# SW6106_A_B_C_Lighting_LED.net
KiCad netlist of a schematic drawn in Altium Designer
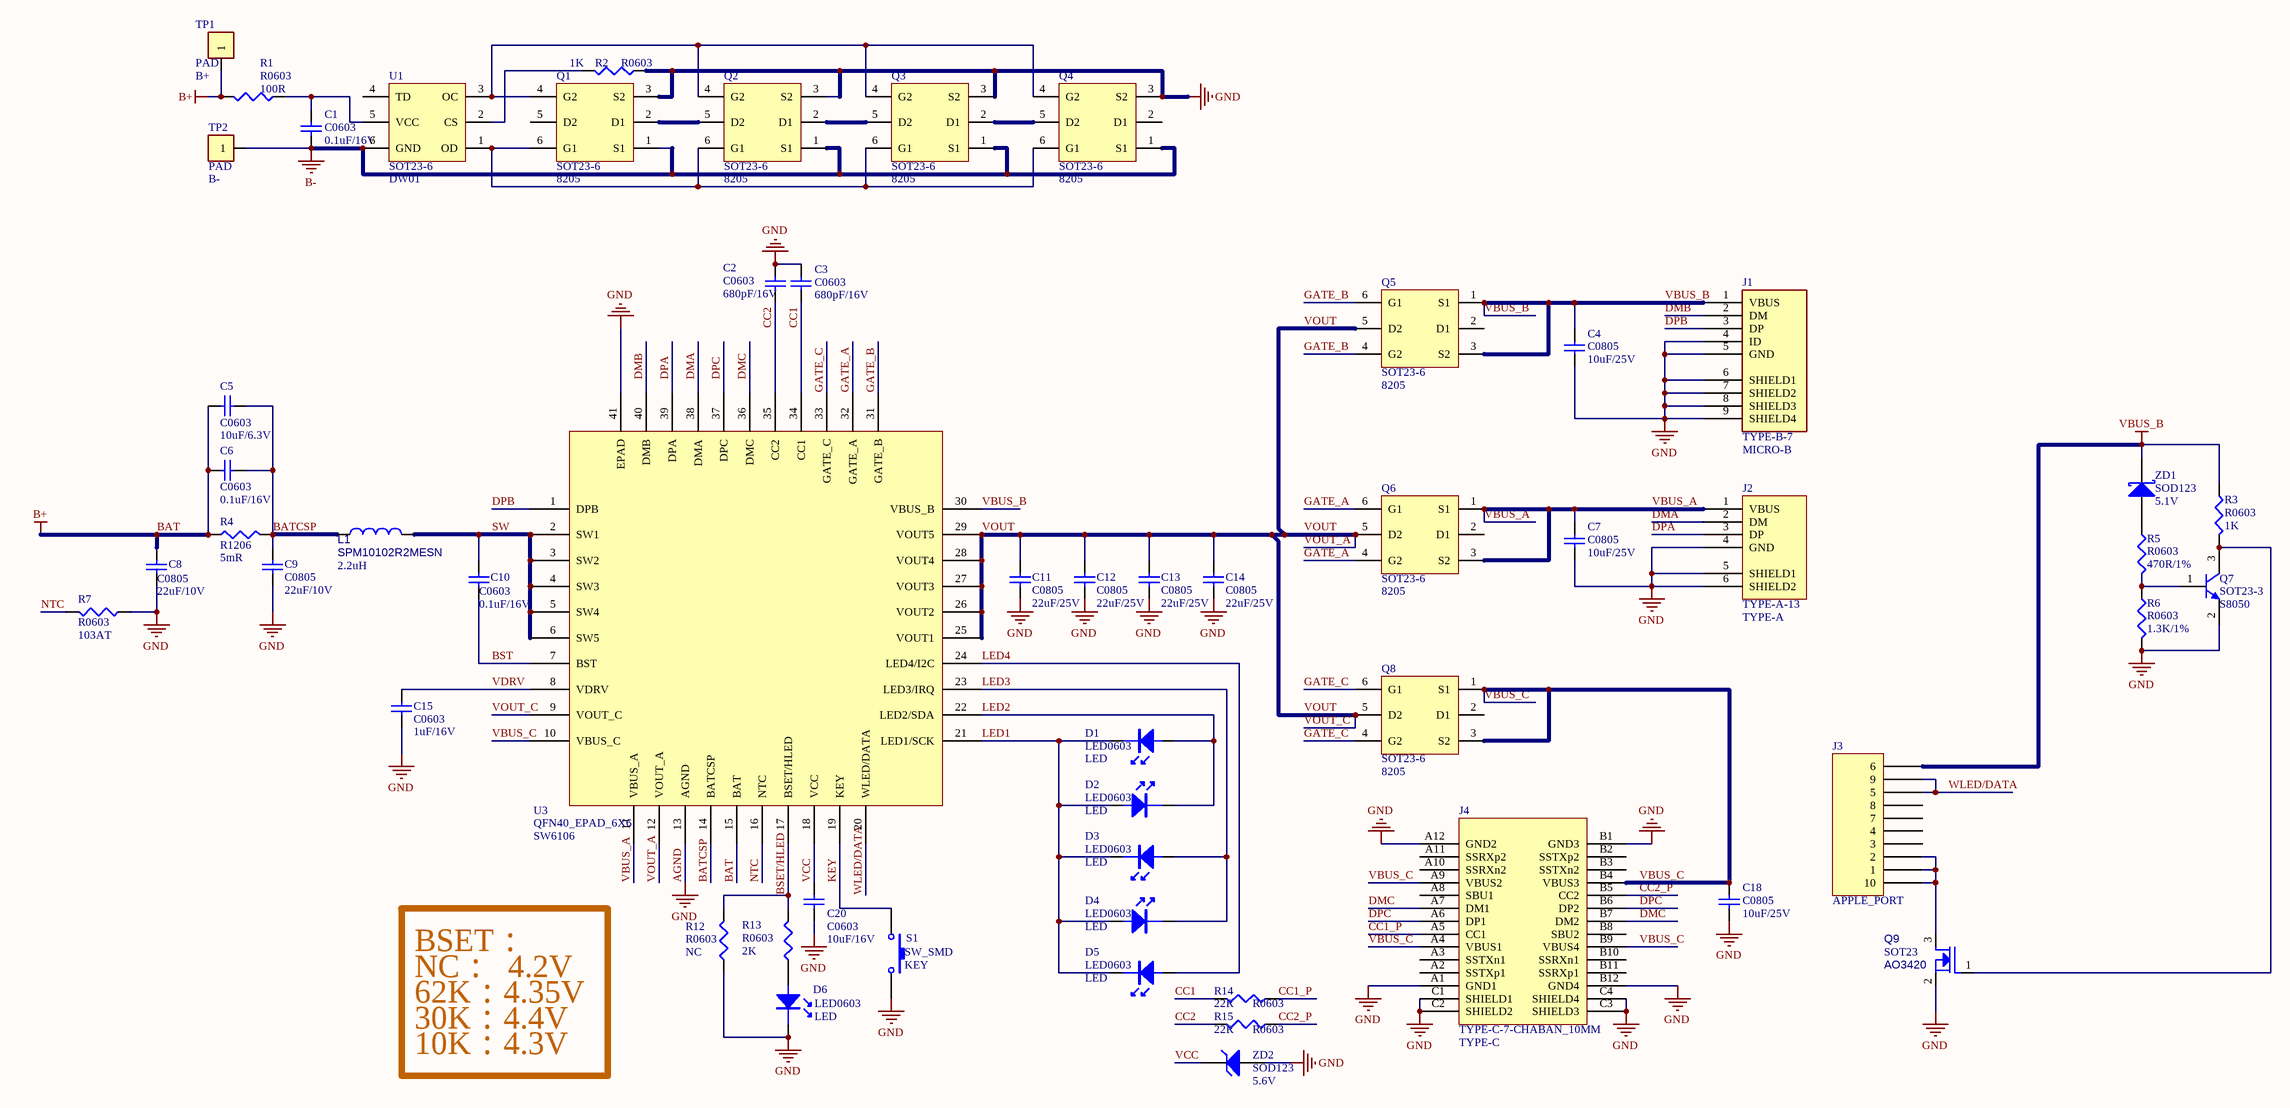
[diagram p0: SW6106+A+B+C+内部解密Lighting+LED.SchDoc]

(export (version "E")
  (design (tool "Eeschema 10.0.6"))
  (components
    (comp (ref "C1")
      (value "C0603")
      (footprint "C0603")
      (description "Capacitor")
      (fields (field (name "ALTIUM_VALUE") "0.1uF/16V") (field (name "PUBLISHER") "Altium Limited"))
      (libsource (lib "*") (part "Cap"))
    )
    (comp (ref "C2")
      (value "C0603")
      (footprint "C0603")
      (description "Capacitor")
      (fields (field (name "ALTIUM_VALUE") "680pF/16V") (field (name "PUBLISHER") "Altium Limited"))
      (libsource (lib "*") (part "CAP0603"))
    )
    (comp (ref "C3")
      (value "C0603")
      (footprint "C0603")
      (description "Capacitor")
      (fields (field (name "ALTIUM_VALUE") "680pF/16V") (field (name "PUBLISHER") "Altium Limited"))
      (libsource (lib "*") (part "CAP0603"))
    )
    (comp (ref "C4")
      (value "C0805")
      (footprint "C0805")
      (description "Capacitor")
      (fields (field (name "ALTIUM_VALUE") "10uF/25V") (field (name "PUBLISHER") "Altium Limited"))
      (libsource (lib "*") (part "CAP0603"))
    )
    (comp (ref "C5")
      (value "C0603")
      (footprint "C0603")
      (description "Capacitor")
      (fields (field (name "ALTIUM_VALUE") "10uF/6.3V") (field (name "PUBLISHER") "Altium Limited"))
      (libsource (lib "*") (part "CAP0603"))
    )
    (comp (ref "C6")
      (value "C0603")
      (footprint "C0603")
      (description "Capacitor")
      (fields (field (name "ALTIUM_VALUE") "0.1uF/16V") (field (name "PUBLISHER") "Altium Limited"))
      (libsource (lib "*") (part "CAP0603"))
    )
    (comp (ref "C7")
      (value "C0805")
      (footprint "C0805")
      (description "Capacitor")
      (fields (field (name "ALTIUM_VALUE") "10uF/25V") (field (name "PUBLISHER") "Altium Limited"))
      (libsource (lib "*") (part "CAP0603"))
    )
    (comp (ref "C8")
      (value "C0805")
      (footprint "C0805")
      (description "Capacitor")
      (fields (field (name "ALTIUM_VALUE") "22uF/10V") (field (name "PUBLISHER") "Altium Limited"))
      (libsource (lib "*") (part "CAP0805"))
    )
    (comp (ref "C9")
      (value "C0805")
      (footprint "C0805")
      (description "Capacitor")
      (fields (field (name "ALTIUM_VALUE") "22uF/10V") (field (name "PUBLISHER") "Altium Limited"))
      (libsource (lib "*") (part "CAP0805"))
    )
    (comp (ref "C10")
      (value "C0603")
      (footprint "C0603")
      (description "Capacitor")
      (fields (field (name "ALTIUM_VALUE") "0.1uF/16V") (field (name "PUBLISHER") "Altium Limited"))
      (libsource (lib "*") (part "CAP0603"))
    )
    (comp (ref "C11")
      (value "C0805")
      (footprint "C0805")
      (description "Capacitor")
      (fields (field (name "ALTIUM_VALUE") "22uF/25V") (field (name "PUBLISHER") "Altium Limited"))
      (libsource (lib "*") (part "CAP0805"))
    )
    (comp (ref "C12")
      (value "C0805")
      (footprint "C0805")
      (description "Capacitor")
      (fields (field (name "ALTIUM_VALUE") "22uF/25V") (field (name "PUBLISHER") "Altium Limited"))
      (libsource (lib "*") (part "CAP0805"))
    )
    (comp (ref "C13")
      (value "C0805")
      (footprint "C0805")
      (description "Capacitor")
      (fields (field (name "ALTIUM_VALUE") "22uF/25V") (field (name "PUBLISHER") "Altium Limited"))
      (libsource (lib "*") (part "CAP0805"))
    )
    (comp (ref "C14")
      (value "C0805")
      (footprint "C0805")
      (description "Capacitor")
      (fields (field (name "ALTIUM_VALUE") "22uF/25V") (field (name "PUBLISHER") "Altium Limited"))
      (libsource (lib "*") (part "CAP0805"))
    )
    (comp (ref "C15")
      (value "C0603")
      (footprint "C0603")
      (description "Capacitor")
      (fields (field (name "ALTIUM_VALUE") "1uF/16V") (field (name "PUBLISHER") "Altium Limited"))
      (libsource (lib "*") (part "CAP0603"))
    )
    (comp (ref "C18")
      (value "C0805")
      (footprint "C0805")
      (description "Capacitor")
      (fields (field (name "ALTIUM_VALUE") "10uF/25V") (field (name "PUBLISHER") "Altium Limited"))
      (libsource (lib "*") (part "CAP0603"))
    )
    (comp (ref "C20")
      (value "C0603")
      (footprint "C0603")
      (description "Capacitor")
      (fields (field (name "ALTIUM_VALUE") "10uF/16V") (field (name "PUBLISHER") "Altium Limited"))
      (libsource (lib "*") (part "CAP0603"))
    )
    (comp (ref "D1") (value "LED") (footprint "LED0603") (libsource (lib "*") (part "LED")))
    (comp (ref "D2") (value "LED") (footprint "LED0603") (libsource (lib "*") (part "LED")))
    (comp (ref "D3") (value "LED") (footprint "LED0603") (libsource (lib "*") (part "LED")))
    (comp (ref "D4") (value "LED") (footprint "LED0603") (libsource (lib "*") (part "LED")))
    (comp (ref "D5") (value "LED") (footprint "LED0603") (libsource (lib "*") (part "LED")))
    (comp (ref "D6") (value "LED") (footprint "LED0603") (libsource (lib "*") (part "LED")))
    (comp (ref "J1")
      (value "MICRO-B")
      (footprint "TYPE-B-7")
      (fields (field (name "FOOTPRINTF") "TYPE-B-7") (field (name "Comment") "USB_MICRO_B"))
      (libsource (lib "*") (part "USB_MICRO_B"))
    )
    (comp (ref "J2")
      (value "TYPE-A")
      (footprint "TYPE-A-13")
      (fields (field (name "FOOTPRINF") "TYPE-A-13") (field (name "Comment") "TYPE-A-1"))
      (libsource (lib "*") (part "TYPE-A-1"))
    )
    (comp (ref "J3") (value "APPLE_PORT") (libsource (lib "TEST") (part "APPLE_PORT")))
    (comp (ref "J4")
      (value "TYPE-C")
      (footprint "TYPE-C-7-CHABAN_10MM")
      (libsource (lib "*") (part "TYPE-C"))
    )
    (comp (ref "L1")
      (value "SPM10102R2MESN")
      (footprint "INDUCTOR_SPM1010")
      (fields (field (name "ALTIUM_VALUE") "2.2uH"))
      (libsource (lib "*") (part "INDUCTOR"))
    )
    (comp (ref "Q1")
      (value "8205")
      (footprint "SOT23-6")
      (fields (field (name "FOOTPRINF") "SOT23-6"))
      (libsource (lib "") (part "8205B_1"))
    )
    (comp (ref "Q2")
      (value "8205")
      (footprint "SOT23-6")
      (fields (field (name "FOOTPRINF") "SOT23-6"))
      (libsource (lib "") (part "8205B_1"))
    )
    (comp (ref "Q3")
      (value "8205")
      (footprint "SOT23-6")
      (fields (field (name "FOOTPRINF") "SOT23-6"))
      (libsource (lib "") (part "8205B_1"))
    )
    (comp (ref "Q4")
      (value "8205")
      (footprint "SOT23-6")
      (fields (field (name "FOOTPRINF") "SOT23-6"))
      (libsource (lib "") (part "8205B_1"))
    )
    (comp (ref "Q5")
      (value "8205")
      (footprint "SOT23-6")
      (fields (field (name "FOOTPRINF") "SOT23-6"))
      (libsource (lib "*") (part "8205B"))
    )
    (comp (ref "Q6")
      (value "8205")
      (footprint "SOT23-6")
      (fields (field (name "FOOTPRINF") "SOT23-6"))
      (libsource (lib "*") (part "8205B"))
    )
    (comp (ref "Q7")
      (value "S8050")
      (footprint "SOT23-3")
      (description "NPN General Purpose Amplifier")
      (fields (field (name "PUBLISHER") "Altium Limited"))
      (libsource (lib "Miscellaneous Devices") (part "2N3904"))
    )
    (comp (ref "Q8")
      (value "8205")
      (footprint "SOT23-6")
      (fields (field (name "FOOTPRINF") "SOT23-6"))
      (libsource (lib "*") (part "8205B"))
    )
    (comp (ref "Q9") (value "AO3420") (footprint "SOT23") (libsource (lib "智融科技有限公司原理图库") (part "MOSFET_N")))
    (comp (ref "R1")
      (value "R0603")
      (footprint "R0603")
      (description "Resistor")
      (fields (field (name "ALTIUM_VALUE") "100R") (field (name "PUBLISHER") "Altium Limited"))
      (libsource (lib "*") (part "Res3"))
    )
    (comp (ref "R2")
      (value "R0603")
      (footprint "R0603")
      (description "Resistor")
      (fields (field (name "ALTIUM_VALUE") "1K") (field (name "PUBLISHER") "Altium Limited"))
      (libsource (lib "*") (part "Res3"))
    )
    (comp (ref "R3")
      (value "R0603")
      (footprint "R0603")
      (description "Resistor")
      (fields (field (name "ALTIUM_VALUE") "1K") (field (name "PUBLISHER") "Altium Limited"))
      (libsource (lib "Miscellaneous Devices") (part "Res3"))
    )
    (comp (ref "R4")
      (value "R1206")
      (footprint "R1206")
      (description "Resistor")
      (fields (field (name "ALTIUM_VALUE") "5mR") (field (name "PUBLISHER") "Altium Limited"))
      (libsource (lib "*") (part "RES"))
    )
    (comp (ref "R5")
      (value "R0603")
      (footprint "R0603")
      (description "Resistor")
      (fields (field (name "ALTIUM_VALUE") "470R/1%") (field (name "PUBLISHER") "Altium Limited"))
      (libsource (lib "Miscellaneous Devices") (part "Res3"))
    )
    (comp (ref "R6")
      (value "R0603")
      (footprint "R0603")
      (description "Resistor")
      (fields (field (name "ALTIUM_VALUE") "1.3K/1%") (field (name "PUBLISHER") "Altium Limited"))
      (libsource (lib "Miscellaneous Devices") (part "Res3"))
    )
    (comp (ref "R7")
      (value "R0603")
      (footprint "R0603")
      (description "Resistor")
      (fields (field (name "ALTIUM_VALUE") "103AT") (field (name "PUBLISHER") "Altium Limited"))
      (libsource (lib "*") (part "RES"))
    )
    (comp (ref "R12")
      (value "R0603")
      (footprint "R0603")
      (description "Resistor")
      (fields (field (name "ALTIUM_VALUE") "NC") (field (name "PUBLISHER") "Altium Limited"))
      (libsource (lib "*") (part "RES"))
    )
    (comp (ref "R13")
      (value "R0603")
      (footprint "R0603")
      (description "Resistor")
      (fields (field (name "ALTIUM_VALUE") "2K") (field (name "PUBLISHER") "Altium Limited"))
      (libsource (lib "*") (part "RES"))
    )
    (comp (ref "R14")
      (value "R0603")
      (footprint "R0603")
      (description "Resistor")
      (fields (field (name "ALTIUM_VALUE") "22R") (field (name "PUBLISHER") "Altium Limited"))
      (libsource (lib "*") (part "RES"))
    )
    (comp (ref "R15")
      (value "R0603")
      (footprint "R0603")
      (description "Resistor")
      (fields (field (name "ALTIUM_VALUE") "22R") (field (name "PUBLISHER") "Altium Limited"))
      (libsource (lib "*") (part "RES"))
    )
    (comp (ref "S1")
      (value "KEY")
      (footprint "SW_SMD")
      (fields (field (name "FOOTPRINF") "SW_SMD"))
      (libsource (lib "*") (part "SW K"))
    )
    (comp (ref "TP1") (value "B+") (footprint "PAD") (libsource (lib "*") (part "Test Point")))
    (comp (ref "TP2") (value "B-") (footprint "PAD") (libsource (lib "") (part "Test Point_1")))
    (comp (ref "U1")
      (value "DW01")
      (footprint "SOT23-6")
      (fields (field (name "FOOTPRINF") "SOT23-6"))
      (libsource (lib "*") (part "DW01"))
    )
    (comp (ref "U3")
      (value "SW6106")
      (footprint "QFN40_EPAD_6X6")
      (libsource (lib "TEST") (part "SW6106_AFC"))
    )
    (comp (ref "ZD1")
      (value "5.1V")
      (footprint "SOD123")
      (description "Schottky Rectifier")
      (fields (field (name "Comment") "Diode 11DQ03") (field (name "PUBLISHER") "Altium Limited"))
      (libsource (lib "Miscellaneous Devices") (part "Diode 11DQ03"))
    )
    (comp (ref "ZD2")
      (value "SOD123")
      (footprint "SOD-123")
      (description "Zener Diode")
      (fields (field (name "ALTIUM_UNNAMED_1") "5.6V"))
      (libsource (lib "Miscellaneous Devices") (part "D Zener"))
    )
  )
  (nets
    (net (code "1") (name "/BATCSP") (class "Default")
      (node (ref "C5") (pin "2") (pinfunction "2_2") (pintype "passive"))
      (node (ref "C6") (pin "2") (pinfunction "2_2") (pintype "passive"))
      (node (ref "C9") (pin "2") (pinfunction "2_2") (pintype "passive"))
      (node (ref "L1") (pin "1") (pinfunction "1_1") (pintype "passive"))
      (node (ref "R4") (pin "2") (pinfunction "2_2") (pintype "passive"))
      (node (ref "U3") (pin "14") (pinfunction "BATCSP_14") (pintype "passive"))
    )
    (net (code "2") (name "/BSET{slash}HLED") (class "Default")
      (node (ref "R12") (pin "2") (pinfunction "2_2") (pintype "passive"))
      (node (ref "R13") (pin "2") (pinfunction "2_2") (pintype "passive"))
      (node (ref "U3") (pin "17") (pinfunction "BSET/HLED_17") (pintype "passive"))
    )
    (net (code "3") (name "/BST") (class "Default")
      (node (ref "C10") (pin "1") (pinfunction "1_1") (pintype "passive"))
      (node (ref "U3") (pin "7") (pinfunction "BST_7") (pintype "passive"))
    )
    (net (code "4") (name "/CC1") (class "Default")
      (node (ref "C3") (pin "1") (pinfunction "1_1") (pintype "passive"))
      (node (ref "R14") (pin "2") (pinfunction "2_2") (pintype "passive"))
      (node (ref "U3") (pin "34") (pinfunction "CC1_34") (pintype "passive"))
    )
    (net (code "5") (name "/CC1_P") (class "Default")
      (node (ref "J4") (pin "A5") (pinfunction "CC1_A5") (pintype "passive"))
      (node (ref "R14") (pin "1") (pinfunction "1_1") (pintype "passive"))
    )
    (net (code "6") (name "/CC2") (class "Default")
      (node (ref "C2") (pin "1") (pinfunction "1_1") (pintype "passive"))
      (node (ref "R15") (pin "2") (pinfunction "2_2") (pintype "passive"))
      (node (ref "U3") (pin "35") (pinfunction "CC2_35") (pintype "passive"))
    )
    (net (code "7") (name "/CC2_P") (class "Default")
      (node (ref "J4") (pin "B5") (pinfunction "CC2_B5") (pintype "passive"))
      (node (ref "R15") (pin "1") (pinfunction "1_1") (pintype "passive"))
    )
    (net (code "8") (name "/DMA") (class "Default")
      (node (ref "J2") (pin "2") (pinfunction "DM_2") (pintype "passive"))
      (node (ref "U3") (pin "38") (pinfunction "DMA_38") (pintype "passive"))
    )
    (net (code "9") (name "/DMB") (class "Default")
      (node (ref "J1") (pin "2") (pinfunction "DM_2") (pintype "passive"))
      (node (ref "U3") (pin "40") (pinfunction "DMB_40") (pintype "passive"))
    )
    (net (code "10") (name "/DMC") (class "Default")
      (node (ref "J4") (pin "A7") (pinfunction "DM1_A7") (pintype "passive"))
      (node (ref "J4") (pin "B7") (pinfunction "DM2_B7") (pintype "passive"))
      (node (ref "U3") (pin "36") (pinfunction "DMC_36") (pintype "passive"))
    )
    (net (code "11") (name "/DPA") (class "Default")
      (node (ref "J2") (pin "3") (pinfunction "DP_3") (pintype "passive"))
      (node (ref "U3") (pin "39") (pinfunction "DPA_39") (pintype "passive"))
    )
    (net (code "12") (name "/DPB") (class "Default")
      (node (ref "J1") (pin "3") (pinfunction "DP_3") (pintype "passive"))
      (node (ref "U3") (pin "1") (pinfunction "DPB_1") (pintype "passive"))
    )
    (net (code "13") (name "/DPC") (class "Default")
      (node (ref "J4") (pin "A6") (pinfunction "DP1_A6") (pintype "passive"))
      (node (ref "J4") (pin "B6") (pinfunction "DP2_B6") (pintype "passive"))
      (node (ref "U3") (pin "37") (pinfunction "DPC_37") (pintype "passive"))
    )
    (net (code "14") (name "/GATE_A") (class "Default")
      (node (ref "Q6") (pin "4") (pinfunction "G2_4") (pintype "passive"))
      (node (ref "Q6") (pin "6") (pinfunction "G1_6") (pintype "passive"))
      (node (ref "U3") (pin "32") (pinfunction "GATE_A_32") (pintype "passive"))
    )
    (net (code "15") (name "/GATE_B") (class "Default")
      (node (ref "Q5") (pin "4") (pinfunction "G2_4") (pintype "passive"))
      (node (ref "Q5") (pin "6") (pinfunction "G1_6") (pintype "passive"))
      (node (ref "U3") (pin "31") (pinfunction "GATE_B_31") (pintype "passive"))
    )
    (net (code "16") (name "/GATE_C") (class "Default")
      (node (ref "Q8") (pin "4") (pinfunction "G2_4") (pintype "passive"))
      (node (ref "Q8") (pin "6") (pinfunction "G1_6") (pintype "passive"))
      (node (ref "U3") (pin "33") (pinfunction "GATE_C_33") (pintype "passive"))
    )
    (net (code "17") (name "/KEY") (class "Default")
      (node (ref "S1") (pin "1") (pinfunction "1_1") (pintype "passive"))
      (node (ref "U3") (pin "19") (pinfunction "KEY_19") (pintype "passive"))
    )
    (net (code "18") (name "/LED1") (class "Default")
      (node (ref "D1") (pin "2") (pinfunction "K_2") (pintype "passive"))
      (node (ref "D2") (pin "1") (pinfunction "A_1") (pintype "passive"))
      (node (ref "D3") (pin "2") (pinfunction "K_2") (pintype "passive"))
      (node (ref "D4") (pin "1") (pinfunction "A_1") (pintype "passive"))
      (node (ref "D5") (pin "2") (pinfunction "K_2") (pintype "passive"))
      (node (ref "U3") (pin "21") (pinfunction "LED1/SCK_21") (pintype "passive"))
    )
    (net (code "19") (name "/LED2") (class "Default")
      (node (ref "D1") (pin "1") (pinfunction "A_1") (pintype "passive"))
      (node (ref "D2") (pin "2") (pinfunction "K_2") (pintype "passive"))
      (node (ref "U3") (pin "22") (pinfunction "LED2/SDA_22") (pintype "passive"))
    )
    (net (code "20") (name "/LED3") (class "Default")
      (node (ref "D3") (pin "1") (pinfunction "A_1") (pintype "passive"))
      (node (ref "D4") (pin "2") (pinfunction "K_2") (pintype "passive"))
      (node (ref "U3") (pin "23") (pinfunction "LED3/IRQ_23") (pintype "passive"))
    )
    (net (code "21") (name "/LED4") (class "Default")
      (node (ref "D5") (pin "1") (pinfunction "A_1") (pintype "passive"))
      (node (ref "U3") (pin "24") (pinfunction "LED4/I2C_24") (pintype "passive"))
    )
    (net (code "22") (name "/NTC") (class "Default")
      (node (ref "R7") (pin "2") (pinfunction "2_2") (pintype "passive"))
      (node (ref "U3") (pin "16") (pinfunction "NTC_16") (pintype "passive"))
    )
    (net (code "23") (name "/SW") (class "Default")
      (node (ref "C10") (pin "2") (pinfunction "2_2") (pintype "passive"))
      (node (ref "L1") (pin "2") (pinfunction "2_2") (pintype "passive"))
      (node (ref "U3") (pin "2") (pinfunction "SW1_2") (pintype "passive"))
      (node (ref "U3") (pin "3") (pinfunction "SW2_3") (pintype "passive"))
      (node (ref "U3") (pin "4") (pinfunction "SW3_4") (pintype "passive"))
      (node (ref "U3") (pin "5") (pinfunction "SW4_5") (pintype "passive"))
      (node (ref "U3") (pin "6") (pinfunction "SW5_6") (pintype "passive"))
    )
    (net (code "24") (name "/VBUS_A") (class "Default")
      (node (ref "C7") (pin "2") (pinfunction "2_2") (pintype "passive"))
      (node (ref "J2") (pin "1") (pinfunction "VBUS_1") (pintype "passive"))
      (node (ref "Q6") (pin "1") (pinfunction "S1_1") (pintype "passive"))
      (node (ref "Q6") (pin "3") (pinfunction "S2_3") (pintype "passive"))
      (node (ref "U3") (pin "11") (pinfunction "VBUS_A_11") (pintype "passive"))
    )
    (net (code "25") (name "/VBUS_C") (class "Default")
      (node (ref "C18") (pin "2") (pinfunction "2_2") (pintype "passive"))
      (node (ref "J4") (pin "A4") (pinfunction "VBUS1_A4") (pintype "passive"))
      (node (ref "J4") (pin "A9") (pinfunction "VBUS2_A9") (pintype "passive"))
      (node (ref "J4") (pin "B4") (pinfunction "VBUS3_B4") (pintype "passive"))
      (node (ref "J4") (pin "B9") (pinfunction "VBUS4_B9") (pintype "passive"))
      (node (ref "Q8") (pin "1") (pinfunction "S1_1") (pintype "passive"))
      (node (ref "Q8") (pin "3") (pinfunction "S2_3") (pintype "passive"))
      (node (ref "U3") (pin "10") (pinfunction "VBUS_C_10") (pintype "passive"))
    )
    (net (code "26") (name "/VCC") (class "Default")
      (node (ref "C20") (pin "2") (pinfunction "2_2") (pintype "passive"))
      (node (ref "U3") (pin "18") (pinfunction "VCC_18") (pintype "passive"))
      (node (ref "ZD2") (pin "2") (pinfunction "K_2") (pintype "passive"))
    )
    (net (code "27") (name "/VDRV") (class "Default")
      (node (ref "C15") (pin "2") (pinfunction "2_2") (pintype "passive"))
      (node (ref "U3") (pin "8") (pinfunction "VDRV_8") (pintype "passive"))
    )
    (net (code "28") (name "/VOUT") (class "Default")
      (node (ref "C11") (pin "2") (pinfunction "2_2") (pintype "passive"))
      (node (ref "C12") (pin "2") (pinfunction "2_2") (pintype "passive"))
      (node (ref "C13") (pin "2") (pinfunction "2_2") (pintype "passive"))
      (node (ref "C14") (pin "2") (pinfunction "2_2") (pintype "passive"))
      (node (ref "Q5") (pin "5") (pinfunction "D2_5") (pintype "passive"))
      (node (ref "Q6") (pin "5") (pinfunction "D2_5") (pintype "passive"))
      (node (ref "Q8") (pin "5") (pinfunction "D2_5") (pintype "passive"))
      (node (ref "U3") (pin "12") (pinfunction "VOUT_A_12") (pintype "passive"))
      (node (ref "U3") (pin "25") (pinfunction "VOUT1_25") (pintype "passive"))
      (node (ref "U3") (pin "26") (pinfunction "VOUT2_26") (pintype "passive"))
      (node (ref "U3") (pin "27") (pinfunction "VOUT3_27") (pintype "passive"))
      (node (ref "U3") (pin "28") (pinfunction "VOUT4_28") (pintype "passive"))
      (node (ref "U3") (pin "29") (pinfunction "VOUT5_29") (pintype "passive"))
      (node (ref "U3") (pin "9") (pinfunction "VOUT_C_9") (pintype "passive"))
    )
    (net (code "29") (name "/WLED{slash}DATA") (class "Default")
      (node (ref "J3") (pin "5") (pinfunction "5_5") (pintype "passive"))
      (node (ref "J3") (pin "9") (pinfunction "9_9") (pintype "passive"))
      (node (ref "U3") (pin "20") (pinfunction "WLED/DATA_20") (pintype "passive"))
    )
    (net (code "30") (name "B+") (class "Default")
      (node (ref "C5") (pin "1") (pinfunction "1_1") (pintype "passive"))
      (node (ref "C6") (pin "1") (pinfunction "1_1") (pintype "passive"))
      (node (ref "C8") (pin "2") (pinfunction "2_2") (pintype "passive"))
      (node (ref "R1") (pin "2") (pinfunction "2_2") (pintype "passive"))
      (node (ref "R4") (pin "1") (pinfunction "1_1") (pintype "passive"))
      (node (ref "TP1") (pin "1") (pinfunction "1_1") (pintype "passive"))
      (node (ref "U3") (pin "15") (pinfunction "BAT_15") (pintype "passive"))
    )
    (net (code "31") (name "B-") (class "Default")
      (node (ref "C1") (pin "1") (pinfunction "1_1") (pintype "passive"))
      (node (ref "Q1") (pin "1") (pinfunction "S1_1") (pintype "passive"))
      (node (ref "Q2") (pin "1") (pinfunction "S1_1") (pintype "passive"))
      (node (ref "Q3") (pin "1") (pinfunction "S1_1") (pintype "passive"))
      (node (ref "Q4") (pin "1") (pinfunction "S1_1") (pintype "passive"))
      (node (ref "TP2") (pin "1") (pinfunction "1_1") (pintype "passive"))
      (node (ref "U1") (pin "6") (pinfunction "GND_6") (pintype "passive"))
    )
    (net (code "32") (name "GND") (class "Default")
      (node (ref "C11") (pin "1") (pinfunction "1_1") (pintype "passive"))
      (node (ref "C12") (pin "1") (pinfunction "1_1") (pintype "passive"))
      (node (ref "C13") (pin "1") (pinfunction "1_1") (pintype "passive"))
      (node (ref "C14") (pin "1") (pinfunction "1_1") (pintype "passive"))
      (node (ref "C15") (pin "1") (pinfunction "1_1") (pintype "passive"))
      (node (ref "C18") (pin "1") (pinfunction "1_1") (pintype "passive"))
      (node (ref "C2") (pin "2") (pinfunction "2_2") (pintype "passive"))
      (node (ref "C20") (pin "1") (pinfunction "1_1") (pintype "passive"))
      (node (ref "C3") (pin "2") (pinfunction "2_2") (pintype "passive"))
      (node (ref "C4") (pin "1") (pinfunction "1_1") (pintype "passive"))
      (node (ref "C7") (pin "1") (pinfunction "1_1") (pintype "passive"))
      (node (ref "C8") (pin "1") (pinfunction "1_1") (pintype "passive"))
      (node (ref "C9") (pin "1") (pinfunction "1_1") (pintype "passive"))
      (node (ref "D6") (pin "2") (pinfunction "K_2") (pintype "passive"))
      (node (ref "J1") (pin "4") (pinfunction "ID_4") (pintype "passive"))
      (node (ref "J1") (pin "5") (pinfunction "GND_5") (pintype "passive"))
      (node (ref "J1") (pin "6") (pinfunction "SHIELD1_6") (pintype "passive"))
      (node (ref "J1") (pin "7") (pinfunction "SHIELD2_7") (pintype "passive"))
      (node (ref "J1") (pin "8") (pinfunction "SHIELD3_8") (pintype "passive"))
      (node (ref "J1") (pin "9") (pinfunction "SHIELD4_9") (pintype "passive"))
      (node (ref "J2") (pin "4") (pinfunction "GND_4") (pintype "passive"))
      (node (ref "J2") (pin "5") (pinfunction "SHIELD1_5") (pintype "passive"))
      (node (ref "J2") (pin "6") (pinfunction "SHIELD2_6") (pintype "passive"))
      (node (ref "J4") (pin "A1") (pinfunction "GND1_A1") (pintype "passive"))
      (node (ref "J4") (pin "A12") (pinfunction "GND2_A12") (pintype "passive"))
      (node (ref "J4") (pin "B1") (pinfunction "GND3_B1") (pintype "passive"))
      (node (ref "J4") (pin "B12") (pinfunction "GND4_B12") (pintype "passive"))
      (node (ref "J4") (pin "C1") (pinfunction "SHIELD1_C1") (pintype "passive"))
      (node (ref "J4") (pin "C2") (pinfunction "SHIELD2_C2") (pintype "passive"))
      (node (ref "J4") (pin "C3") (pinfunction "SHIELD3_C3") (pintype "passive"))
      (node (ref "J4") (pin "C4") (pinfunction "SHIELD4_C4") (pintype "passive"))
      (node (ref "Q1") (pin "3") (pinfunction "S2_3") (pintype "passive"))
      (node (ref "Q2") (pin "3") (pinfunction "S2_3") (pintype "passive"))
      (node (ref "Q3") (pin "3") (pinfunction "S2_3") (pintype "passive"))
      (node (ref "Q4") (pin "3") (pinfunction "S2_3") (pintype "passive"))
      (node (ref "Q7") (pin "2") (pinfunction "E_2") (pintype "passive"))
      (node (ref "Q9") (pin "2") (pinfunction "SOURCE_2") (pintype "passive"))
      (node (ref "R12") (pin "1") (pinfunction "1_1") (pintype "passive"))
      (node (ref "R2") (pin "1") (pinfunction "1_1") (pintype "passive"))
      (node (ref "R6") (pin "2") (pinfunction "2_2") (pintype "passive"))
      (node (ref "R7") (pin "1") (pinfunction "1_1") (pintype "passive"))
      (node (ref "S1") (pin "2") (pinfunction "2_2") (pintype "passive"))
      (node (ref "U3") (pin "13") (pinfunction "AGND_13") (pintype "passive"))
      (node (ref "U3") (pin "41") (pinfunction "EPAD_41") (pintype "passive"))
      (node (ref "ZD2") (pin "1") (pinfunction "A_1") (pintype "passive"))
    )
    (net (code "33") (name "Net-(D6-A)") (class "Default")
      (node (ref "D6") (pin "1") (pinfunction "A_1") (pintype "passive"))
      (node (ref "R13") (pin "1") (pinfunction "1_1") (pintype "passive"))
    )
    (net (code "34") (name "Net-(Q1-D1)") (class "Default")
      (node (ref "Q1") (pin "2") (pinfunction "D1_2") (pintype "passive"))
      (node (ref "Q2") (pin "5") (pinfunction "D2_5") (pintype "passive"))
    )
    (net (code "35") (name "Net-(Q1-G1)") (class "Default")
      (node (ref "Q1") (pin "6") (pinfunction "G1_6") (pintype "passive"))
      (node (ref "Q2") (pin "6") (pinfunction "G1_6") (pintype "passive"))
      (node (ref "Q3") (pin "6") (pinfunction "G1_6") (pintype "passive"))
      (node (ref "Q4") (pin "6") (pinfunction "G1_6") (pintype "passive"))
      (node (ref "U1") (pin "1") (pinfunction "OD_1") (pintype "passive"))
    )
    (net (code "36") (name "Net-(Q1-G2)") (class "Default")
      (node (ref "Q1") (pin "4") (pinfunction "G2_4") (pintype "passive"))
      (node (ref "Q2") (pin "4") (pinfunction "G2_4") (pintype "passive"))
      (node (ref "Q3") (pin "4") (pinfunction "G2_4") (pintype "passive"))
      (node (ref "Q4") (pin "4") (pinfunction "G2_4") (pintype "passive"))
      (node (ref "U1") (pin "3") (pinfunction "OC_3") (pintype "passive"))
    )
    (net (code "37") (name "Net-(Q2-D1)") (class "Default")
      (node (ref "Q2") (pin "2") (pinfunction "D1_2") (pintype "passive"))
      (node (ref "Q3") (pin "5") (pinfunction "D2_5") (pintype "passive"))
    )
    (net (code "38") (name "Net-(Q3-D1)") (class "Default")
      (node (ref "Q3") (pin "2") (pinfunction "D1_2") (pintype "passive"))
      (node (ref "Q4") (pin "5") (pinfunction "D2_5") (pintype "passive"))
    )
    (net (code "39") (name "Net-(Q7-B)") (class "Default")
      (node (ref "Q7") (pin "1") (pinfunction "B_1") (pintype "passive"))
      (node (ref "R5") (pin "2") (pinfunction "2_2") (pintype "passive"))
      (node (ref "R6") (pin "1") (pinfunction "1_1") (pintype "passive"))
    )
    (net (code "40") (name "Net-(Q7-C)") (class "Default")
      (node (ref "Q7") (pin "3") (pinfunction "C_3") (pintype "passive"))
      (node (ref "Q9") (pin "1") (pinfunction "GATE_1") (pintype "passive"))
      (node (ref "R3") (pin "2") (pinfunction "2_2") (pintype "passive"))
    )
    (net (code "41") (name "Net-(Q9-DRAIN)") (class "Default")
      (node (ref "J3") (pin "1") (pinfunction "1_1") (pintype "passive"))
      (node (ref "J3") (pin "10") (pinfunction "10_10") (pintype "passive"))
      (node (ref "J3") (pin "2") (pinfunction "2_2") (pintype "passive"))
      (node (ref "Q9") (pin "3") (pinfunction "DRAIN_3") (pintype "passive"))
    )
    (net (code "42") (name "Net-(U1-CS)") (class "Default")
      (node (ref "R2") (pin "2") (pinfunction "2_2") (pintype "passive"))
      (node (ref "U1") (pin "2") (pinfunction "CS_2") (pintype "passive"))
    )
    (net (code "43") (name "Net-(U1-VCC)") (class "Default")
      (node (ref "C1") (pin "2") (pinfunction "2_2") (pintype "passive"))
      (node (ref "R1") (pin "1") (pinfunction "1_1") (pintype "passive"))
      (node (ref "U1") (pin "5") (pinfunction "VCC_5") (pintype "passive"))
    )
    (net (code "44") (name "Net-(ZD1-A)") (class "Default")
      (node (ref "R5") (pin "1") (pinfunction "1_1") (pintype "passive"))
      (node (ref "ZD1") (pin "1") (pinfunction "A_1") (pintype "passive"))
    )
    (net (code "45") (name "VBUS_B") (class "Default")
      (node (ref "C4") (pin "2") (pinfunction "2_2") (pintype "passive"))
      (node (ref "J1") (pin "1") (pinfunction "VBUS_1") (pintype "passive"))
      (node (ref "J3") (pin "6") (pinfunction "6_6") (pintype "passive"))
      (node (ref "Q5") (pin "1") (pinfunction "S1_1") (pintype "passive"))
      (node (ref "Q5") (pin "3") (pinfunction "S2_3") (pintype "passive"))
      (node (ref "R3") (pin "1") (pinfunction "1_1") (pintype "passive"))
      (node (ref "U3") (pin "30") (pinfunction "VBUS_B_30") (pintype "passive"))
      (node (ref "ZD1") (pin "2") (pinfunction "K_2") (pintype "passive"))
    )
    (net (code "46") (name "unconnected-(J3-Pad3)") (class "Default")
      (node (ref "J3") (pin "3") (pinfunction "3_3") (pintype "passive"))
    )
    (net (code "47") (name "unconnected-(J3-Pad4)") (class "Default")
      (node (ref "J3") (pin "4") (pinfunction "4_4") (pintype "passive"))
    )
    (net (code "48") (name "unconnected-(J3-Pad7)") (class "Default")
      (node (ref "J3") (pin "7") (pinfunction "7_7") (pintype "passive"))
    )
    (net (code "49") (name "unconnected-(J3-Pad8)") (class "Default")
      (node (ref "J3") (pin "8") (pinfunction "8_8") (pintype "passive"))
    )
    (net (code "50") (name "unconnected-(J4-SBU1-PadA8)") (class "Default")
      (node (ref "J4") (pin "A8") (pinfunction "SBU1_A8") (pintype "passive"))
    )
    (net (code "51") (name "unconnected-(J4-SBU2-PadB8)") (class "Default")
      (node (ref "J4") (pin "B8") (pinfunction "SBU2_B8") (pintype "passive"))
    )
    (net (code "52") (name "unconnected-(J4-SSRXn1-PadB10)") (class "Default")
      (node (ref "J4") (pin "B10") (pinfunction "SSRXn1_B10") (pintype "passive"))
    )
    (net (code "53") (name "unconnected-(J4-SSRXn2-PadA10)") (class "Default")
      (node (ref "J4") (pin "A10") (pinfunction "SSRXn2_A10") (pintype "passive"))
    )
    (net (code "54") (name "unconnected-(J4-SSRXp1-PadB11)") (class "Default")
      (node (ref "J4") (pin "B11") (pinfunction "SSRXp1_B11") (pintype "passive"))
    )
    (net (code "55") (name "unconnected-(J4-SSRXp2-PadA11)") (class "Default")
      (node (ref "J4") (pin "A11") (pinfunction "SSRXp2_A11") (pintype "passive"))
    )
    (net (code "56") (name "unconnected-(J4-SSTXn1-PadA3)") (class "Default")
      (node (ref "J4") (pin "A3") (pinfunction "SSTXn1_A3") (pintype "passive"))
    )
    (net (code "57") (name "unconnected-(J4-SSTXn2-PadB3)") (class "Default")
      (node (ref "J4") (pin "B3") (pinfunction "SSTXn2_B3") (pintype "passive"))
    )
    (net (code "58") (name "unconnected-(J4-SSTXp1-PadA2)") (class "Default")
      (node (ref "J4") (pin "A2") (pinfunction "SSTXp1_A2") (pintype "passive"))
    )
    (net (code "59") (name "unconnected-(J4-SSTXp2-PadB2)") (class "Default")
      (node (ref "J4") (pin "B2") (pinfunction "SSTXp2_B2") (pintype "passive"))
    )
    (net (code "60") (name "unconnected-(Q1-D2-Pad5)") (class "Default")
      (node (ref "Q1") (pin "5") (pinfunction "D2_5") (pintype "passive"))
    )
    (net (code "61") (name "unconnected-(Q4-D1-Pad2)") (class "Default")
      (node (ref "Q4") (pin "2") (pinfunction "D1_2") (pintype "passive"))
    )
    (net (code "62") (name "unconnected-(Q5-D1-Pad2)") (class "Default")
      (node (ref "Q5") (pin "2") (pinfunction "D1_2") (pintype "passive"))
    )
    (net (code "63") (name "unconnected-(Q6-D1-Pad2)") (class "Default")
      (node (ref "Q6") (pin "2") (pinfunction "D1_2") (pintype "passive"))
    )
    (net (code "64") (name "unconnected-(Q8-D1-Pad2)") (class "Default")
      (node (ref "Q8") (pin "2") (pinfunction "D1_2") (pintype "passive"))
    )
    (net (code "65") (name "unconnected-(U1-TD-Pad4)") (class "Default")
      (node (ref "U1") (pin "4") (pinfunction "TD_4") (pintype "passive"))
    )
  )
)
